# eTHERNET.net
KiCad netlist of a schematic drawn in Altium Designer
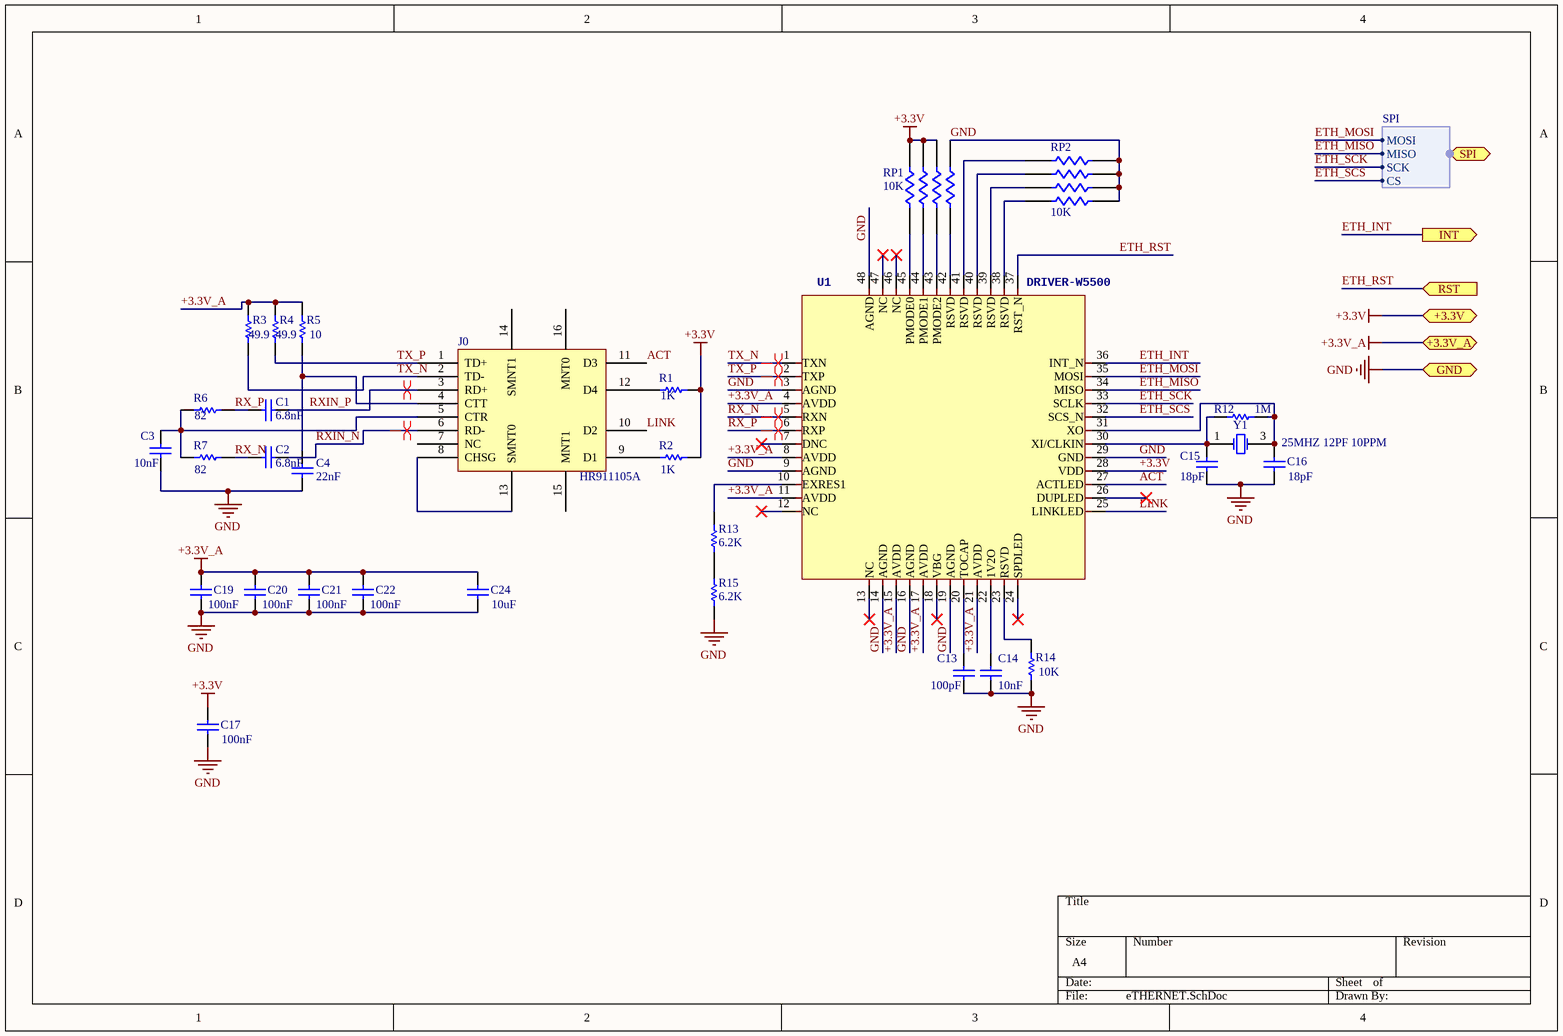
[diagram p0: eTHERNET.SchDoc]

(export (version "E")
  (design (tool "Eeschema 10.0.6"))
  (components
    (comp (ref "C1")
      (value "6.8nF")
      (footprint "C-1608[0603]")
      (description "Capacitor (Semiconductor SIM Model)")
      (fields (field (name "PUBLISHER") "Altium Limited"))
      (libsource (lib "Miscellaneous Devices") (part "Cap Semi"))
    )
    (comp (ref "C2")
      (value "6.8nF")
      (footprint "C-1608[0603]")
      (description "Capacitor (Semiconductor SIM Model)")
      (fields (field (name "PUBLISHER") "Altium Limited"))
      (libsource (lib "Miscellaneous Devices") (part "Cap Semi"))
    )
    (comp (ref "C3")
      (value "10nF")
      (footprint "C-1608[0603]")
      (description "Capacitor (Semiconductor SIM Model)")
      (fields (field (name "PUBLISHER") "Altium Limited"))
      (libsource (lib "Miscellaneous Devices") (part "Cap Semi"))
    )
    (comp (ref "C4")
      (value "22nF")
      (footprint "C-1608[0603]")
      (description "Capacitor (Semiconductor SIM Model)")
      (fields (field (name "PUBLISHER") "Altium Limited"))
      (libsource (lib "Miscellaneous Devices") (part "Cap Semi"))
    )
    (comp (ref "C13")
      (value "100pF")
      (footprint "C-1608[0603]")
      (description "Capacitor (Semiconductor SIM Model)")
      (fields (field (name "PUBLISHER") "Altium Limited"))
      (libsource (lib "Miscellaneous Devices") (part "Cap Semi"))
    )
    (comp (ref "C14")
      (value "10nF")
      (footprint "C-1608[0603]")
      (description "Capacitor (Semiconductor SIM Model)")
      (fields (field (name "PUBLISHER") "Altium Limited"))
      (libsource (lib "Miscellaneous Devices") (part "Cap Semi"))
    )
    (comp (ref "C15")
      (value "18pF")
      (footprint "C-1608[0603]")
      (description "Capacitor (Semiconductor SIM Model)")
      (fields (field (name "PUBLISHER") "Altium Limited"))
      (libsource (lib "Miscellaneous Devices") (part "Cap Semi"))
    )
    (comp (ref "C16")
      (value "18pF")
      (footprint "C-1608[0603]")
      (description "Capacitor (Semiconductor SIM Model)")
      (fields (field (name "PUBLISHER") "Altium Limited"))
      (libsource (lib "Miscellaneous Devices") (part "Cap Semi"))
    )
    (comp (ref "C17")
      (value "100nF")
      (footprint "C-1608[0603]")
      (description "Capacitor (Semiconductor SIM Model)")
      (fields (field (name "PUBLISHER") "Altium Limited"))
      (libsource (lib "Miscellaneous Devices") (part "Cap Semi"))
    )
    (comp (ref "C19")
      (value "100nF")
      (footprint "C-1608[0603]")
      (description "Capacitor (Semiconductor SIM Model)")
      (fields (field (name "PUBLISHER") "Altium Limited"))
      (libsource (lib "Miscellaneous Devices") (part "Cap Semi"))
    )
    (comp (ref "C20")
      (value "100nF")
      (footprint "C-1608[0603]")
      (description "Capacitor (Semiconductor SIM Model)")
      (fields (field (name "PUBLISHER") "Altium Limited"))
      (libsource (lib "Miscellaneous Devices") (part "Cap Semi"))
    )
    (comp (ref "C21")
      (value "100nF")
      (footprint "C-1608[0603]")
      (description "Capacitor (Semiconductor SIM Model)")
      (fields (field (name "PUBLISHER") "Altium Limited"))
      (libsource (lib "Miscellaneous Devices") (part "Cap Semi"))
    )
    (comp (ref "C22")
      (value "100nF")
      (footprint "C-1608[0603]")
      (description "Capacitor (Semiconductor SIM Model)")
      (fields (field (name "PUBLISHER") "Altium Limited"))
      (libsource (lib "Miscellaneous Devices") (part "Cap Semi"))
    )
    (comp (ref "C24")
      (value "10uF")
      (footprint "C-1608[0603]")
      (description "Capacitor (Semiconductor SIM Model)")
      (fields (field (name "PUBLISHER") "Altium Limited"))
      (libsource (lib "Miscellaneous Devices") (part "Cap Semi"))
    )
    (comp (ref "J0")
      (value "HR911105A")
      (footprint "RJ45-8P8C")
      (libsource (lib "DAUGUTER") (part "RJ45INTLED"))
    )
    (comp (ref "R1")
      (value "1K")
      (footprint "R-1608[0603]")
      (description "Semiconductor Resistor")
      (fields (field (name "PUBLISHER") "Altium Limited"))
      (libsource (lib "Miscellaneous Devices") (part "Res Semi"))
    )
    (comp (ref "R2")
      (value "1K")
      (footprint "R-1608[0603]")
      (description "Semiconductor Resistor")
      (fields (field (name "PUBLISHER") "Altium Limited"))
      (libsource (lib "Miscellaneous Devices") (part "Res Semi"))
    )
    (comp (ref "R3")
      (value "49.9")
      (footprint "R-1608[0603]")
      (description "Semiconductor Resistor")
      (fields (field (name "PUBLISHER") "Altium Limited"))
      (libsource (lib "Miscellaneous Devices") (part "Res Semi"))
    )
    (comp (ref "R4")
      (value "49.9")
      (footprint "R-1608[0603]")
      (description "Semiconductor Resistor")
      (fields (field (name "PUBLISHER") "Altium Limited"))
      (libsource (lib "Miscellaneous Devices") (part "Res Semi"))
    )
    (comp (ref "R5")
      (value "10")
      (footprint "R-1608[0603]")
      (description "Semiconductor Resistor")
      (fields (field (name "PUBLISHER") "Altium Limited"))
      (libsource (lib "Miscellaneous Devices") (part "Res Semi"))
    )
    (comp (ref "R6")
      (value "82")
      (footprint "R-1608[0603]")
      (description "Semiconductor Resistor")
      (fields (field (name "PUBLISHER") "Altium Limited"))
      (libsource (lib "Miscellaneous Devices") (part "Res Semi"))
    )
    (comp (ref "R7")
      (value "82")
      (footprint "R-1608[0603]")
      (description "Semiconductor Resistor")
      (fields (field (name "PUBLISHER") "Altium Limited"))
      (libsource (lib "Miscellaneous Devices") (part "Res Semi"))
    )
    (comp (ref "R12")
      (value "1M")
      (footprint "R-1608[0603]")
      (description "Semiconductor Resistor")
      (fields (field (name "PUBLISHER") "Altium Limited"))
      (libsource (lib "Miscellaneous Devices") (part "Res Semi"))
    )
    (comp (ref "R13")
      (value "6.2K")
      (footprint "R-1608[0603]")
      (description "Semiconductor Resistor")
      (fields (field (name "PUBLISHER") "Altium Limited"))
      (libsource (lib "Miscellaneous Devices") (part "Res Semi"))
    )
    (comp (ref "R14")
      (value "10K")
      (footprint "R-1608[0603]")
      (description "Semiconductor Resistor")
      (fields (field (name "PUBLISHER") "Altium Limited"))
      (libsource (lib "Miscellaneous Devices") (part "Res Semi"))
    )
    (comp (ref "R15")
      (value "6.2K")
      (footprint "R-1608[0603]")
      (description "Semiconductor Resistor")
      (fields (field (name "PUBLISHER") "Altium Limited"))
      (libsource (lib "Miscellaneous Devices") (part "Res Semi"))
    )
    (comp (ref "RP1") (value "10K") (footprint "R0603x4") (libsource (lib "general") (part "RPACK4")))
    (comp (ref "RP2") (value "10K") (footprint "R0603x4") (libsource (lib "general") (part "RPACK4")))
    (comp (ref "U1")
      (value "DRIVER-W5500")
      (footprint "TQFP48_N")
      (libsource (lib "general") (part "DRIVER-W5500"))
    )
    (comp (ref "Y1")
      (value "25MHZ 12PF 10PPM")
      (footprint "XT_3225_4")
      (description "Crystal Oscillator")
      (fields (field (name "PUBLISHER") "Altium Limited"))
      (libsource (lib "Miscellaneous Devices") (part "XTAL"))
    )
  )
  (nets
    (net (code "2") (name "+3.3V") (class "Default")
      (node (ref "C17") (pin "2") (pinfunction "2_2") (pintype "passive"))
      (node (ref "R1") (pin "2") (pinfunction "2_2") (pintype "passive"))
      (node (ref "R2") (pin "2") (pinfunction "2_2") (pintype "passive"))
      (node (ref "RP1") (pin "6") (pinfunction "6_6") (pintype "passive"))
      (node (ref "RP1") (pin "7") (pinfunction "7_7") (pintype "passive"))
      (node (ref "RP1") (pin "8") (pinfunction "8_8") (pintype "passive"))
      (node (ref "U1") (pin "28") (pinfunction "VDD_28") (pintype "passive"))
    )
    (net (code "3") (name "+3.3V_A") (class "Default")
      (node (ref "C19") (pin "2") (pinfunction "2_2") (pintype "passive"))
      (node (ref "C20") (pin "2") (pinfunction "2_2") (pintype "passive"))
      (node (ref "C21") (pin "2") (pinfunction "2_2") (pintype "passive"))
      (node (ref "C22") (pin "2") (pinfunction "2_2") (pintype "passive"))
      (node (ref "C24") (pin "2") (pinfunction "2_2") (pintype "passive"))
      (node (ref "R3") (pin "2") (pinfunction "2_2") (pintype "passive"))
      (node (ref "R4") (pin "2") (pinfunction "2_2") (pintype "passive"))
      (node (ref "R5") (pin "2") (pinfunction "2_2") (pintype "passive"))
      (node (ref "U1") (pin "11") (pinfunction "AVDD_11") (pintype "passive"))
      (node (ref "U1") (pin "15") (pinfunction "AVDD_15") (pintype "passive"))
      (node (ref "U1") (pin "17") (pinfunction "AVDD_17") (pintype "passive"))
      (node (ref "U1") (pin "21") (pinfunction "AVDD_21") (pintype "passive"))
      (node (ref "U1") (pin "4") (pinfunction "AVDD_4") (pintype "passive"))
      (node (ref "U1") (pin "8") (pinfunction "AVDD_8") (pintype "passive"))
    )
    (net (code "4") (name "/ACT") (class "Default")
      (node (ref "J0") (pin "11") (pinfunction "D3_11") (pintype "passive"))
      (node (ref "U1") (pin "27") (pinfunction "ACTLED_27") (pintype "passive"))
    )
    (net (code "5") (name "/ETH_INT") (class "Default")
      (node (ref "U1") (pin "36") (pinfunction "INT_N_36") (pintype "passive"))
    )
    (net (code "6") (name "/ETH_MISO") (class "Default")
      (node (ref "U1") (pin "34") (pinfunction "MISO_34") (pintype "passive"))
    )
    (net (code "7") (name "/ETH_MOSI") (class "Default")
      (node (ref "U1") (pin "35") (pinfunction "MOSI_35") (pintype "passive"))
    )
    (net (code "8") (name "/ETH_RST") (class "Default")
      (node (ref "U1") (pin "37") (pinfunction "RST_N_37") (pintype "passive"))
    )
    (net (code "9") (name "/ETH_SCK") (class "Default")
      (node (ref "U1") (pin "33") (pinfunction "SCLK_33") (pintype "passive"))
    )
    (net (code "10") (name "/ETH_SCS") (class "Default")
      (node (ref "U1") (pin "32") (pinfunction "SCS_N_32") (pintype "passive"))
    )
    (net (code "11") (name "/LINK") (class "Default")
      (node (ref "J0") (pin "10") (pinfunction "D2_10") (pintype "passive"))
      (node (ref "U1") (pin "25") (pinfunction "LINKLED_25") (pintype "passive"))
    )
    (net (code "12") (name "/RXIN_N") (class "Default")
      (node (ref "C2") (pin "2") (pinfunction "2_2") (pintype "passive"))
      (node (ref "J0") (pin "6") (pinfunction "RD-_6") (pintype "passive"))
    )
    (net (code "13") (name "/RXIN_P") (class "Default")
      (node (ref "C1") (pin "2") (pinfunction "2_2") (pintype "passive"))
      (node (ref "J0") (pin "3") (pinfunction "RD+_3") (pintype "passive"))
    )
    (net (code "14") (name "/RX_N") (class "Default")
      (node (ref "C2") (pin "1") (pinfunction "1_1") (pintype "passive"))
      (node (ref "R7") (pin "2") (pinfunction "2_2") (pintype "passive"))
      (node (ref "U1") (pin "5") (pinfunction "RXN_5") (pintype "passive"))
    )
    (net (code "15") (name "/RX_P") (class "Default")
      (node (ref "C1") (pin "1") (pinfunction "1_1") (pintype "passive"))
      (node (ref "R6") (pin "2") (pinfunction "2_2") (pintype "passive"))
      (node (ref "U1") (pin "6") (pinfunction "RXP_6") (pintype "passive"))
    )
    (net (code "16") (name "/TX_N") (class "Default")
      (node (ref "J0") (pin "2") (pinfunction "TD-_2") (pintype "passive"))
      (node (ref "R3") (pin "1") (pinfunction "1_1") (pintype "passive"))
      (node (ref "U1") (pin "1") (pinfunction "TXN_1") (pintype "passive"))
    )
    (net (code "17") (name "/TX_P") (class "Default")
      (node (ref "J0") (pin "1") (pinfunction "TD+_1") (pintype "passive"))
      (node (ref "R4") (pin "1") (pinfunction "1_1") (pintype "passive"))
      (node (ref "U1") (pin "2") (pinfunction "TXP_2") (pintype "passive"))
    )
    (net (code "19") (name "GND") (class "Default")
      (node (ref "C13") (pin "1") (pinfunction "1_1") (pintype "passive"))
      (node (ref "C14") (pin "1") (pinfunction "1_1") (pintype "passive"))
      (node (ref "C15") (pin "1") (pinfunction "1_1") (pintype "passive"))
      (node (ref "C16") (pin "1") (pinfunction "1_1") (pintype "passive"))
      (node (ref "C17") (pin "1") (pinfunction "1_1") (pintype "passive"))
      (node (ref "C19") (pin "1") (pinfunction "1_1") (pintype "passive"))
      (node (ref "C20") (pin "1") (pinfunction "1_1") (pintype "passive"))
      (node (ref "C21") (pin "1") (pinfunction "1_1") (pintype "passive"))
      (node (ref "C22") (pin "1") (pinfunction "1_1") (pintype "passive"))
      (node (ref "C24") (pin "1") (pinfunction "1_1") (pintype "passive"))
      (node (ref "C3") (pin "1") (pinfunction "1_1") (pintype "passive"))
      (node (ref "C4") (pin "1") (pinfunction "1_1") (pintype "passive"))
      (node (ref "R14") (pin "2") (pinfunction "2_2") (pintype "passive"))
      (node (ref "R15") (pin "2") (pinfunction "2_2") (pintype "passive"))
      (node (ref "RP1") (pin "5") (pinfunction "5_5") (pintype "passive"))
      (node (ref "RP2") (pin "5") (pinfunction "5_5") (pintype "passive"))
      (node (ref "RP2") (pin "6") (pinfunction "6_6") (pintype "passive"))
      (node (ref "RP2") (pin "7") (pinfunction "7_7") (pintype "passive"))
      (node (ref "RP2") (pin "8") (pinfunction "8_8") (pintype "passive"))
      (node (ref "U1") (pin "14") (pinfunction "AGND_14") (pintype "passive"))
      (node (ref "U1") (pin "16") (pinfunction "AGND_16") (pintype "passive"))
      (node (ref "U1") (pin "19") (pinfunction "AGND_19") (pintype "passive"))
      (node (ref "U1") (pin "29") (pinfunction "GND_29") (pintype "passive"))
      (node (ref "U1") (pin "3") (pinfunction "AGND_3") (pintype "passive"))
      (node (ref "U1") (pin "48") (pinfunction "AGND_48") (pintype "passive"))
      (node (ref "U1") (pin "9") (pinfunction "AGND_9") (pintype "passive"))
    )
    (net (code "20") (name "Net-(J0-CHSG)") (class "Default")
      (node (ref "J0") (pin "13") (pinfunction "SMNT0_13") (pintype "passive"))
      (node (ref "J0") (pin "8") (pinfunction "CHSG_8") (pintype "passive"))
    )
    (net (code "21") (name "Net-(J0-CTR)") (class "Default")
      (node (ref "C3") (pin "2") (pinfunction "2_2") (pintype "passive"))
      (node (ref "J0") (pin "5") (pinfunction "CTR_5") (pintype "passive"))
      (node (ref "R6") (pin "1") (pinfunction "1_1") (pintype "passive"))
      (node (ref "R7") (pin "1") (pinfunction "1_1") (pintype "passive"))
    )
    (net (code "22") (name "Net-(J0-CTT)") (class "Default")
      (node (ref "C4") (pin "2") (pinfunction "2_2") (pintype "passive"))
      (node (ref "J0") (pin "4") (pinfunction "CTT_4") (pintype "passive"))
      (node (ref "R5") (pin "1") (pinfunction "1_1") (pintype "passive"))
    )
    (net (code "23") (name "Net-(J0-D1)") (class "Default")
      (node (ref "J0") (pin "9") (pinfunction "D1_9") (pintype "passive"))
      (node (ref "R2") (pin "1") (pinfunction "1_1") (pintype "passive"))
    )
    (net (code "24") (name "Net-(J0-D4)") (class "Default")
      (node (ref "J0") (pin "12") (pinfunction "D4_12") (pintype "passive"))
      (node (ref "R1") (pin "1") (pinfunction "1_1") (pintype "passive"))
    )
    (net (code "25") (name "Net-(R13-Pad2)") (class "Default")
      (node (ref "R13") (pin "2") (pinfunction "2_2") (pintype "passive"))
      (node (ref "R15") (pin "1") (pinfunction "1_1") (pintype "passive"))
    )
    (net (code "26") (name "Net-(R14-Pad1)") (class "Default")
      (node (ref "R14") (pin "1") (pinfunction "1_1") (pintype "passive"))
      (node (ref "U1") (pin "23") (pinfunction "RSVD_23") (pintype "passive"))
    )
    (net (code "27") (name "Net-(RP1-Pad4)") (class "Default")
      (node (ref "RP1") (pin "4") (pinfunction "4_4") (pintype "passive"))
      (node (ref "U1") (pin "42") (pinfunction "RSVD_42") (pintype "passive"))
    )
    (net (code "28") (name "Net-(RP2-Pad1)") (class "Default")
      (node (ref "RP2") (pin "1") (pinfunction "1_1") (pintype "passive"))
      (node (ref "U1") (pin "41") (pinfunction "RSVD_41") (pintype "passive"))
    )
    (net (code "29") (name "Net-(RP2-Pad2)") (class "Default")
      (node (ref "RP2") (pin "2") (pinfunction "2_2") (pintype "passive"))
      (node (ref "U1") (pin "40") (pinfunction "RSVD_40") (pintype "passive"))
    )
    (net (code "30") (name "Net-(RP2-Pad3)") (class "Default")
      (node (ref "RP2") (pin "3") (pinfunction "3_3") (pintype "passive"))
      (node (ref "U1") (pin "39") (pinfunction "RSVD_39") (pintype "passive"))
    )
    (net (code "31") (name "Net-(RP2-Pad4)") (class "Default")
      (node (ref "RP2") (pin "4") (pinfunction "4_4") (pintype "passive"))
      (node (ref "U1") (pin "38") (pinfunction "RSVD_38") (pintype "passive"))
    )
    (net (code "32") (name "Net-(U1-1V2O)") (class "Default")
      (node (ref "C14") (pin "2") (pinfunction "2_2") (pintype "passive"))
      (node (ref "U1") (pin "22") (pinfunction "1V2O_22") (pintype "passive"))
    )
    (net (code "33") (name "Net-(U1-EXRES1)") (class "Default")
      (node (ref "R13") (pin "1") (pinfunction "1_1") (pintype "passive"))
      (node (ref "U1") (pin "10") (pinfunction "EXRES1_10") (pintype "passive"))
    )
    (net (code "34") (name "Net-(U1-PMODE0)") (class "Default")
      (node (ref "RP1") (pin "1") (pinfunction "1_1") (pintype "passive"))
      (node (ref "U1") (pin "45") (pinfunction "PMODE0_45") (pintype "passive"))
    )
    (net (code "35") (name "Net-(U1-PMODE1)") (class "Default")
      (node (ref "RP1") (pin "2") (pinfunction "2_2") (pintype "passive"))
      (node (ref "U1") (pin "44") (pinfunction "PMODE1_44") (pintype "passive"))
    )
    (net (code "36") (name "Net-(U1-PMODE2)") (class "Default")
      (node (ref "RP1") (pin "3") (pinfunction "3_3") (pintype "passive"))
      (node (ref "U1") (pin "43") (pinfunction "PMODE2_43") (pintype "passive"))
    )
    (net (code "37") (name "Net-(U1-TOCAP)") (class "Default")
      (node (ref "C13") (pin "2") (pinfunction "2_2") (pintype "passive"))
      (node (ref "U1") (pin "20") (pinfunction "TOCAP_20") (pintype "passive"))
    )
    (net (code "38") (name "Net-(U1-XI{slash}CLKIN)") (class "Default")
      (node (ref "C15") (pin "2") (pinfunction "2_2") (pintype "passive"))
      (node (ref "R12") (pin "1") (pinfunction "1_1") (pintype "passive"))
      (node (ref "U1") (pin "30") (pinfunction "XI/CLKIN_30") (pintype "passive"))
      (node (ref "Y1") (pin "1") (pinfunction "OSC1_1") (pintype "passive"))
    )
    (net (code "39") (name "Net-(U1-XO)") (class "Default")
      (node (ref "C16") (pin "2") (pinfunction "2_2") (pintype "passive"))
      (node (ref "R12") (pin "2") (pinfunction "2_2") (pintype "passive"))
      (node (ref "U1") (pin "31") (pinfunction "XO_31") (pintype "passive"))
      (node (ref "Y1") (pin "3") (pinfunction "OSC2_3") (pintype "passive"))
    )
    (net (code "40") (name "unconnected-(J0-MNT0-Pad16)") (class "Default")
      (node (ref "J0") (pin "16") (pinfunction "MNT0_16") (pintype "passive"))
    )
    (net (code "41") (name "unconnected-(J0-MNT1-Pad15)") (class "Default")
      (node (ref "J0") (pin "15") (pinfunction "MNT1_15") (pintype "passive"))
    )
    (net (code "42") (name "unconnected-(J0-NC-Pad7)") (class "Default")
      (node (ref "J0") (pin "7") (pinfunction "NC_7") (pintype "passive"))
    )
    (net (code "43") (name "unconnected-(J0-SMNT1-Pad14)") (class "Default")
      (node (ref "J0") (pin "14") (pinfunction "SMNT1_14") (pintype "passive"))
    )
    (net (code "44") (name "unconnected-(U1-DNC-Pad7)") (class "Default")
      (node (ref "U1") (pin "7") (pinfunction "DNC_7") (pintype "passive+no_connect"))
    )
    (net (code "45") (name "unconnected-(U1-DUPLED-Pad26)") (class "Default")
      (node (ref "U1") (pin "26") (pinfunction "DUPLED_26") (pintype "passive+no_connect"))
    )
    (net (code "46") (name "unconnected-(U1-NC-Pad12)") (class "Default")
      (node (ref "U1") (pin "12") (pinfunction "NC_12") (pintype "passive+no_connect"))
    )
    (net (code "47") (name "unconnected-(U1-NC-Pad13)") (class "Default")
      (node (ref "U1") (pin "13") (pinfunction "NC_13") (pintype "passive+no_connect"))
    )
    (net (code "48") (name "unconnected-(U1-NC-Pad46)") (class "Default")
      (node (ref "U1") (pin "46") (pinfunction "NC_46") (pintype "passive+no_connect"))
    )
    (net (code "49") (name "unconnected-(U1-NC-Pad47)") (class "Default")
      (node (ref "U1") (pin "47") (pinfunction "NC_47") (pintype "passive+no_connect"))
    )
    (net (code "50") (name "unconnected-(U1-SPDLED-Pad24)") (class "Default")
      (node (ref "U1") (pin "24") (pinfunction "SPDLED_24") (pintype "passive+no_connect"))
    )
    (net (code "51") (name "unconnected-(U1-VBG-Pad18)") (class "Default")
      (node (ref "U1") (pin "18") (pinfunction "VBG_18") (pintype "passive+no_connect"))
    )
  )
)
